# Turret_Shield.net
KiCad netlist of a schematic drawn in EAGLE
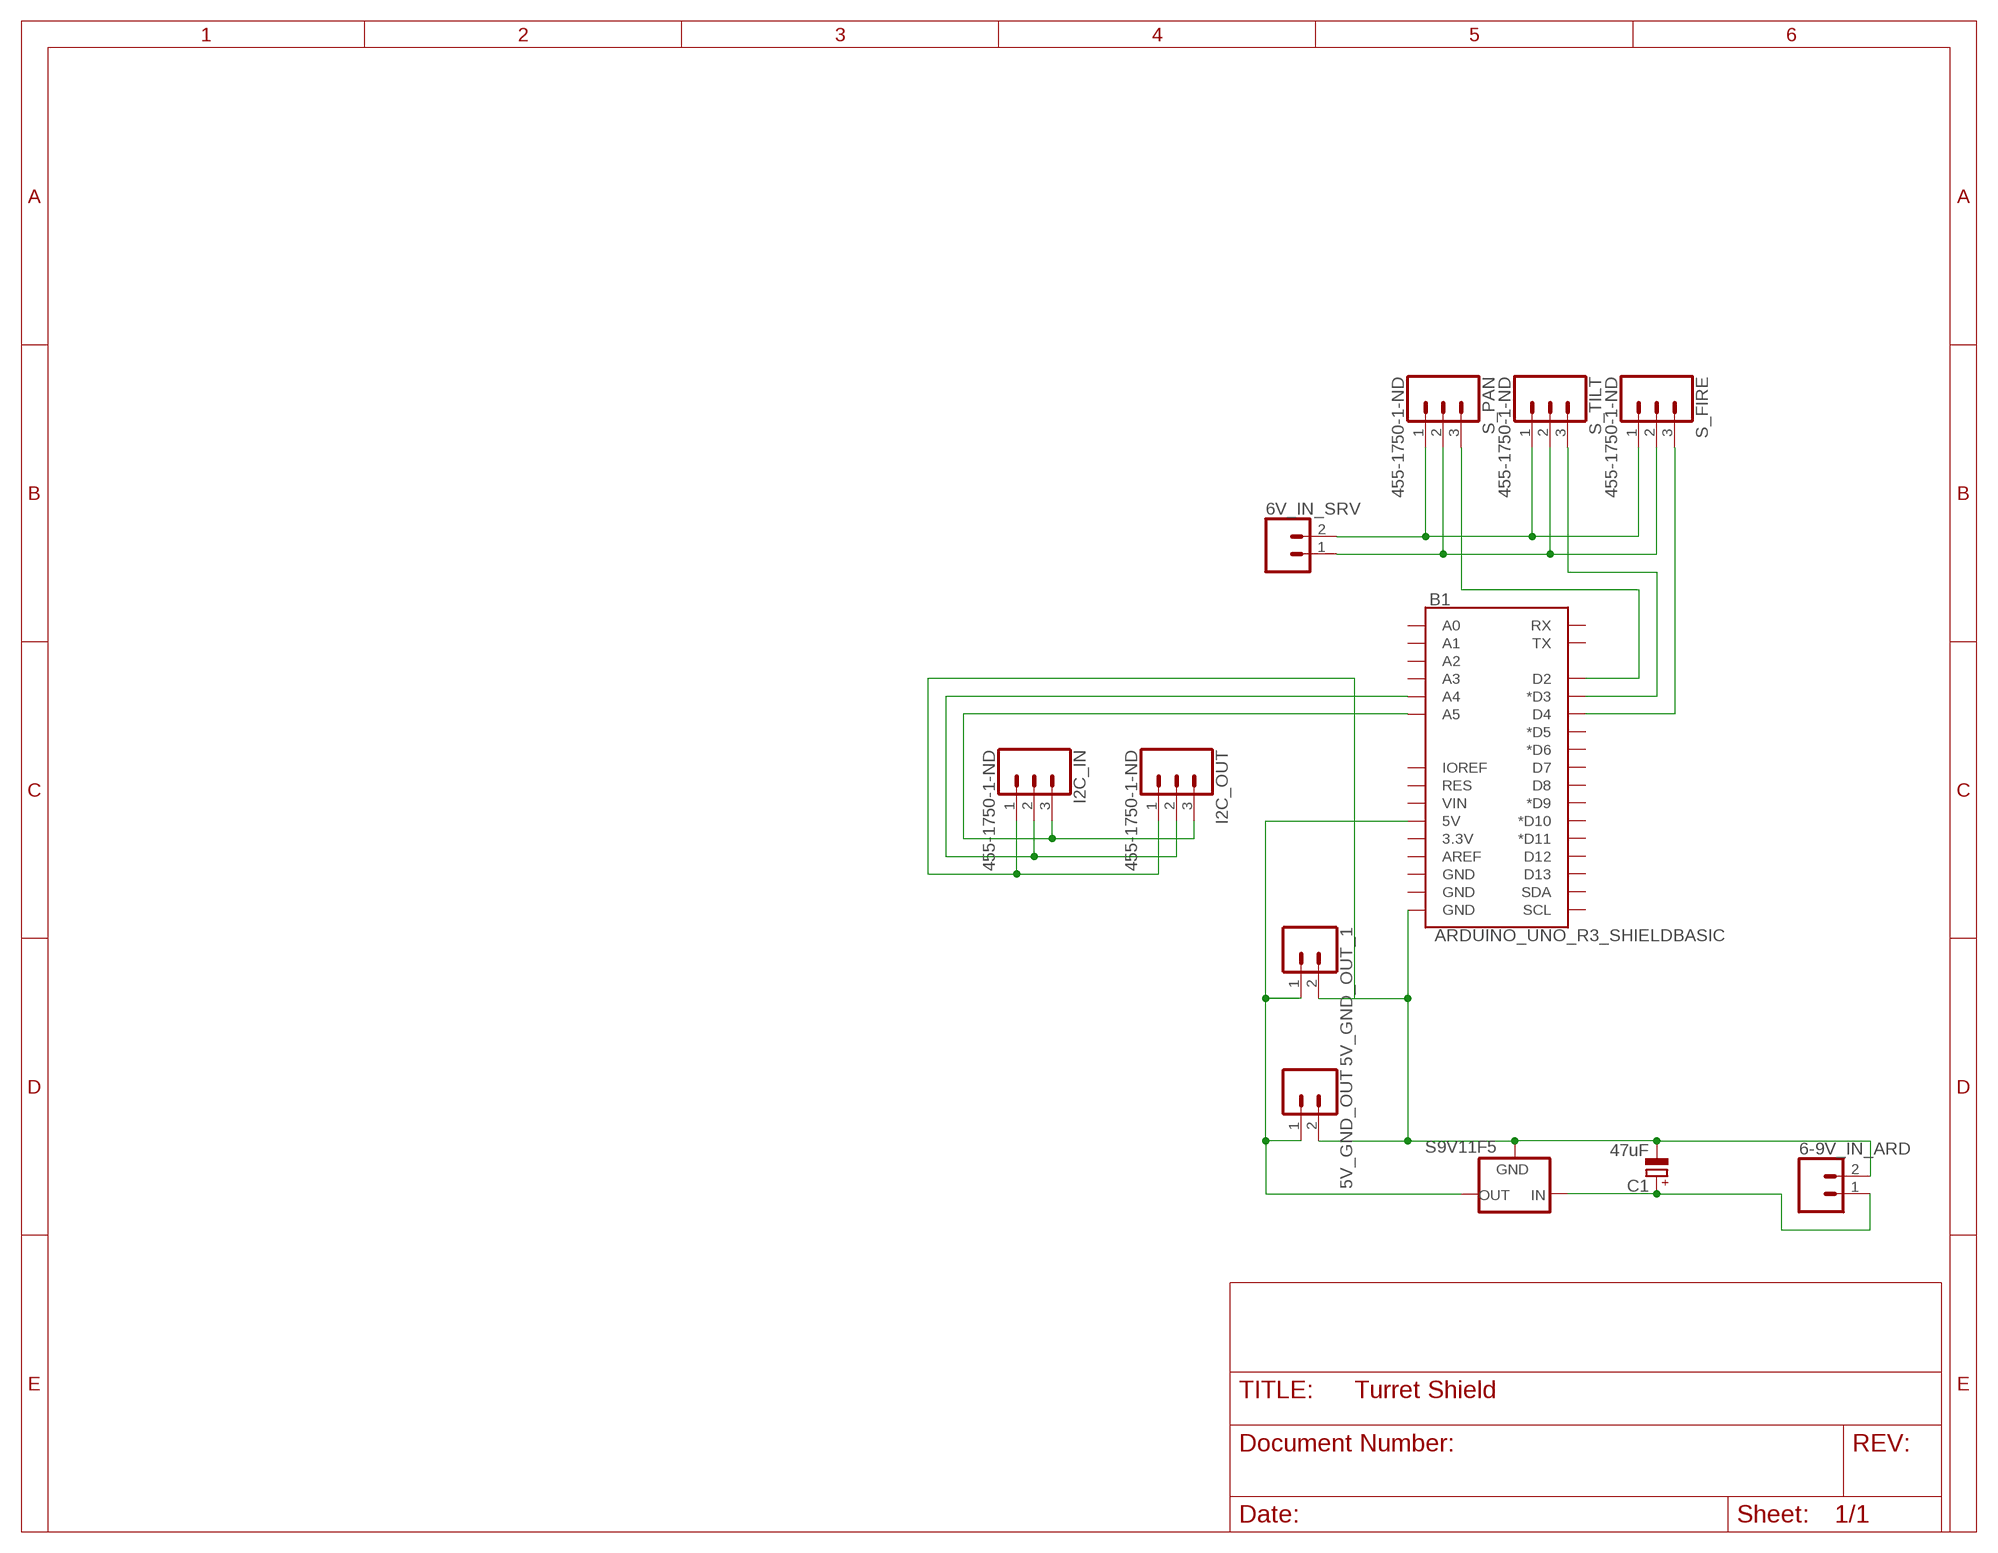
[diagram p0: schematic, sheet 1]

(export (version "E")
  (design (tool "Eeschema 10.0.6"))
  (components
    (comp (ref "5V_GND_OUT")
      (value "CONN_02")
      (footprint "eagle-import:1X02")
      (libsource (lib "eagle-import") (part "CONN_02"))
    )
    (comp (ref "5V_GND_OUT_1")
      (value "CONN_02")
      (footprint "eagle-import:1X02")
      (libsource (lib "eagle-import") (part "CONN_02"))
    )
    (comp (ref "6-9V_IN_ARD")
      (value "CONN_02")
      (footprint "eagle-import:1X02")
      (libsource (lib "eagle-import") (part "CONN_02"))
    )
    (comp (ref "6V_IN_SRV")
      (value "CONN_02")
      (footprint "eagle-import:1X02")
      (libsource (lib "eagle-import") (part "CONN_02"))
    )
    (comp (ref "B1")
      (value "ARDUINO_UNO_R3_SHIELDBASIC")
      (footprint "eagle-import:UNO_R3_SHIELD")
      (libsource (lib "eagle-import") (part "ARDUINO_UNO_R3_SHIELDBASIC"))
    )
    (comp (ref "C1")
      (value "47uF")
      (footprint "eagle-import:E2,5-6")
      (libsource (lib "eagle-import") (part "CPOL-EUE2.5-6"))
    )
    (comp (ref "I2C_IN")
      (value "455-1750-1-ND")
      (footprint "eagle-import:1X03")
      (libsource (lib "eagle-import") (part "CONN_03"))
    )
    (comp (ref "I2C_OUT")
      (value "455-1750-1-ND")
      (footprint "eagle-import:1X03")
      (libsource (lib "eagle-import") (part "CONN_03"))
    )
    (comp (ref "S9V11F5")
      (value "78XXS")
      (footprint "eagle-import:78XXS")
      (libsource (lib "eagle-import") (part "78XXS"))
    )
    (comp (ref "S_FIRE")
      (value "455-1750-1-ND")
      (footprint "eagle-import:1X03")
      (libsource (lib "eagle-import") (part "CONN_03"))
    )
    (comp (ref "S_PAN")
      (value "455-1750-1-ND")
      (footprint "eagle-import:1X03")
      (libsource (lib "eagle-import") (part "CONN_03"))
    )
    (comp (ref "S_TILT")
      (value "455-1750-1-ND")
      (footprint "eagle-import:1X03")
      (libsource (lib "eagle-import") (part "CONN_03"))
    )
  )
  (nets
    (net (code "1") (name "Net-(5V_GND_OUT-Pad1)") (class "Default")
      (node (ref "5V_GND_OUT") (pin "1") (pinfunction "1_1") (pintype "passive"))
      (node (ref "5V_GND_OUT_1") (pin "1") (pinfunction "1_1") (pintype "passive"))
      (node (ref "B1") (pin "5V") (pinfunction "5V_5V") (pintype "bidirectional"))
      (node (ref "S9V11F5") (pin "OUT") (pinfunction "OUT_OUT") (pintype "passive"))
    )
    (net (code "2") (name "Net-(5V_GND_OUT-Pad2)") (class "Default")
      (node (ref "5V_GND_OUT") (pin "2") (pinfunction "2_2") (pintype "passive"))
      (node (ref "5V_GND_OUT_1") (pin "2") (pinfunction "2_2") (pintype "passive"))
      (node (ref "6-9V_IN_ARD") (pin "2") (pinfunction "2_2") (pintype "passive"))
      (node (ref "B1") (pin "GND@0") (pinfunction "GND_GND@0") (pintype "bidirectional"))
      (node (ref "C1") (pin "-") (pinfunction "-_-") (pintype "passive"))
      (node (ref "I2C_IN") (pin "1") (pinfunction "1_1") (pintype "passive"))
      (node (ref "I2C_OUT") (pin "1") (pinfunction "1_1") (pintype "passive"))
      (node (ref "S9V11F5") (pin "GND") (pinfunction "GND_GND") (pintype "input"))
    )
    (net (code "3") (name "Net-(6-9V_IN_ARD-Pad1)") (class "Default")
      (node (ref "6-9V_IN_ARD") (pin "1") (pinfunction "1_1") (pintype "passive"))
      (node (ref "C1") (pin "+") (pinfunction "+_+") (pintype "passive"))
      (node (ref "S9V11F5") (pin "IN") (pinfunction "IN_IN") (pintype "input"))
    )
    (net (code "4") (name "Net-(6V_IN_SRV-Pad1)") (class "Default")
      (node (ref "6V_IN_SRV") (pin "1") (pinfunction "1_1") (pintype "passive"))
      (node (ref "S_FIRE") (pin "2") (pinfunction "2_2") (pintype "passive"))
      (node (ref "S_PAN") (pin "2") (pinfunction "2_2") (pintype "passive"))
      (node (ref "S_TILT") (pin "2") (pinfunction "2_2") (pintype "passive"))
    )
    (net (code "5") (name "Net-(6V_IN_SRV-Pad2)") (class "Default")
      (node (ref "6V_IN_SRV") (pin "2") (pinfunction "2_2") (pintype "passive"))
      (node (ref "S_FIRE") (pin "1") (pinfunction "1_1") (pintype "passive"))
      (node (ref "S_PAN") (pin "1") (pinfunction "1_1") (pintype "passive"))
      (node (ref "S_TILT") (pin "1") (pinfunction "1_1") (pintype "passive"))
    )
    (net (code "6") (name "Net-(B1-*D3)") (class "Default")
      (node (ref "B1") (pin "D3") (pinfunction "*D3_D3") (pintype "bidirectional"))
      (node (ref "S_TILT") (pin "3") (pinfunction "3_3") (pintype "passive"))
    )
    (net (code "7") (name "Net-(B1-PadA4)") (class "Default")
      (node (ref "B1") (pin "A4") (pinfunction "A4_A4") (pintype "bidirectional"))
      (node (ref "I2C_IN") (pin "2") (pinfunction "2_2") (pintype "passive"))
      (node (ref "I2C_OUT") (pin "2") (pinfunction "2_2") (pintype "passive"))
    )
    (net (code "8") (name "Net-(B1-PadA5)") (class "Default")
      (node (ref "B1") (pin "A5") (pinfunction "A5_A5") (pintype "bidirectional"))
      (node (ref "I2C_IN") (pin "3") (pinfunction "3_3") (pintype "passive"))
      (node (ref "I2C_OUT") (pin "3") (pinfunction "3_3") (pintype "passive"))
    )
    (net (code "9") (name "Net-(B1-PadD2)") (class "Default")
      (node (ref "B1") (pin "D2") (pinfunction "D2_D2") (pintype "bidirectional"))
      (node (ref "S_PAN") (pin "3") (pinfunction "3_3") (pintype "passive"))
    )
    (net (code "10") (name "Net-(B1-PadD4)") (class "Default")
      (node (ref "B1") (pin "D4") (pinfunction "D4_D4") (pintype "bidirectional"))
      (node (ref "S_FIRE") (pin "3") (pinfunction "3_3") (pintype "passive"))
    )
    (net (code "11") (name "unconnected-(B1-*D5-PadD5)") (class "Default")
      (node (ref "B1") (pin "D5") (pinfunction "*D5_D5") (pintype "bidirectional"))
    )
    (net (code "12") (name "unconnected-(B1-*D6-PadD6)") (class "Default")
      (node (ref "B1") (pin "D6") (pinfunction "*D6_D6") (pintype "bidirectional"))
    )
    (net (code "13") (name "unconnected-(B1-*D9-PadD9)") (class "Default")
      (node (ref "B1") (pin "D9") (pinfunction "*D9_D9") (pintype "bidirectional"))
    )
    (net (code "14") (name "unconnected-(B1-*D10-PadD10)") (class "Default")
      (node (ref "B1") (pin "D10") (pinfunction "*D10_D10") (pintype "bidirectional"))
    )
    (net (code "15") (name "unconnected-(B1-*D11-PadD11)") (class "Default")
      (node (ref "B1") (pin "D11") (pinfunction "*D11_D11") (pintype "bidirectional"))
    )
    (net (code "16") (name "unconnected-(B1-GND-PadGND@1)") (class "Default")
      (node (ref "B1") (pin "GND@1") (pinfunction "GND_GND@1") (pintype "bidirectional"))
    )
    (net (code "17") (name "unconnected-(B1-GND-PadGND@2)") (class "Default")
      (node (ref "B1") (pin "GND@2") (pinfunction "GND_GND@2") (pintype "bidirectional"))
    )
    (net (code "18") (name "unconnected-(B1-Pad3.3V)") (class "Default")
      (node (ref "B1") (pin "3.3V") (pinfunction "3.3V_3.3V") (pintype "bidirectional"))
    )
    (net (code "19") (name "unconnected-(B1-PadA0)") (class "Default")
      (node (ref "B1") (pin "A0") (pinfunction "A0_A0") (pintype "bidirectional"))
    )
    (net (code "20") (name "unconnected-(B1-PadA1)") (class "Default")
      (node (ref "B1") (pin "A1") (pinfunction "A1_A1") (pintype "bidirectional"))
    )
    (net (code "21") (name "unconnected-(B1-PadA2)") (class "Default")
      (node (ref "B1") (pin "A2") (pinfunction "A2_A2") (pintype "bidirectional"))
    )
    (net (code "22") (name "unconnected-(B1-PadA3)") (class "Default")
      (node (ref "B1") (pin "A3") (pinfunction "A3_A3") (pintype "bidirectional"))
    )
    (net (code "23") (name "unconnected-(B1-PadAREF)") (class "Default")
      (node (ref "B1") (pin "AREF") (pinfunction "AREF_AREF") (pintype "bidirectional"))
    )
    (net (code "24") (name "unconnected-(B1-PadD7)") (class "Default")
      (node (ref "B1") (pin "D7") (pinfunction "D7_D7") (pintype "bidirectional"))
    )
    (net (code "25") (name "unconnected-(B1-PadD8)") (class "Default")
      (node (ref "B1") (pin "D8") (pinfunction "D8_D8") (pintype "bidirectional"))
    )
    (net (code "26") (name "unconnected-(B1-PadD12)") (class "Default")
      (node (ref "B1") (pin "D12") (pinfunction "D12_D12") (pintype "bidirectional"))
    )
    (net (code "27") (name "unconnected-(B1-PadD13)") (class "Default")
      (node (ref "B1") (pin "D13") (pinfunction "D13_D13") (pintype "bidirectional"))
    )
    (net (code "28") (name "unconnected-(B1-PadIOREF)") (class "Default")
      (node (ref "B1") (pin "IOREF") (pinfunction "IOREF_IOREF") (pintype "bidirectional"))
    )
    (net (code "29") (name "unconnected-(B1-PadRES)") (class "Default")
      (node (ref "B1") (pin "RES") (pinfunction "RES_RES") (pintype "bidirectional"))
    )
    (net (code "30") (name "unconnected-(B1-PadRX)") (class "Default")
      (node (ref "B1") (pin "RX") (pinfunction "RX_RX") (pintype "bidirectional"))
    )
    (net (code "31") (name "unconnected-(B1-PadSCL)") (class "Default")
      (node (ref "B1") (pin "SCL") (pinfunction "SCL_SCL") (pintype "bidirectional"))
    )
    (net (code "32") (name "unconnected-(B1-PadSDA)") (class "Default")
      (node (ref "B1") (pin "SDA") (pinfunction "SDA_SDA") (pintype "bidirectional"))
    )
    (net (code "33") (name "unconnected-(B1-PadTX)") (class "Default")
      (node (ref "B1") (pin "TX") (pinfunction "TX_TX") (pintype "bidirectional"))
    )
    (net (code "34") (name "unconnected-(B1-PadVIN)") (class "Default")
      (node (ref "B1") (pin "VIN") (pinfunction "VIN_VIN") (pintype "bidirectional"))
    )
  )
)
